# dig100-logic.net
KiCad netlist of a schematic drawn in EAGLE
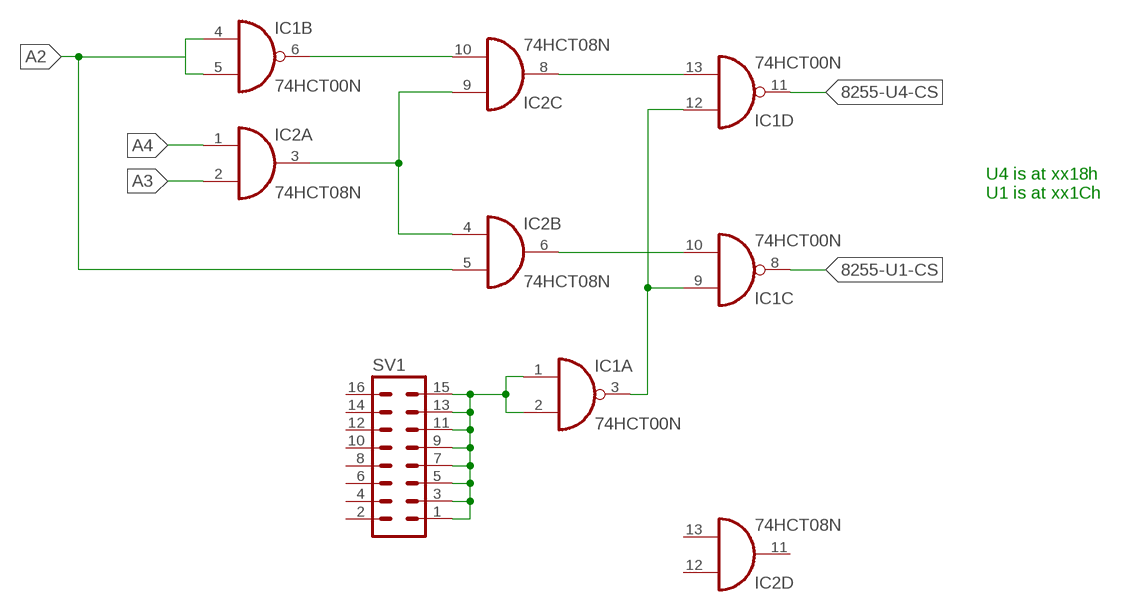
[diagram p0: schematic, sheet 1]

(export (version "E")
  (design (tool "Eeschema 10.0.6"))
  (components
    (comp (ref "IC1")
      (value "74HCT00N")
      (footprint "eagle-import:DIL14")
      (libsource (lib "eagle-import") (part "7400NHCT"))
    )
    (comp (ref "IC2")
      (value "74HCT08N")
      (footprint "eagle-import:DIL14")
      (libsource (lib "eagle-import") (part "7408NHCT"))
    )
    (comp (ref "SV1")
      (value "MA08-2")
      (footprint "eagle-import:MA08-2")
      (libsource (lib "eagle-import") (part "MA08-2"))
    )
  )
  (nets
    (net (code "1") (name "8255-U1-CS") (class "Default")
      (node (ref "IC1") (pin "8") (pinfunction "O_8") (pintype "output"))
    )
    (net (code "2") (name "8255-U4-CS") (class "Default")
      (node (ref "IC1") (pin "11") (pinfunction "O_11") (pintype "output"))
    )
    (net (code "3") (name "A2") (class "Default")
      (node (ref "IC1") (pin "4") (pinfunction "I0_4") (pintype "input"))
      (node (ref "IC1") (pin "5") (pinfunction "I1_5") (pintype "input"))
      (node (ref "IC2") (pin "5") (pinfunction "I1_5") (pintype "input"))
    )
    (net (code "4") (name "A3") (class "Default")
      (node (ref "IC2") (pin "2") (pinfunction "I1_2") (pintype "input"))
    )
    (net (code "5") (name "A4") (class "Default")
      (node (ref "IC2") (pin "1") (pinfunction "I0_1") (pintype "input"))
    )
    (net (code "6") (name "Net-(IC1A-I0)") (class "Default")
      (node (ref "IC1") (pin "1") (pinfunction "I0_1") (pintype "input"))
      (node (ref "IC1") (pin "2") (pinfunction "I1_2") (pintype "input"))
      (node (ref "SV1") (pin "1") (pinfunction "1_1") (pintype "passive"))
      (node (ref "SV1") (pin "11") (pinfunction "11_11") (pintype "passive"))
      (node (ref "SV1") (pin "13") (pinfunction "13_13") (pintype "passive"))
      (node (ref "SV1") (pin "15") (pinfunction "15_15") (pintype "passive"))
      (node (ref "SV1") (pin "3") (pinfunction "3_3") (pintype "passive"))
      (node (ref "SV1") (pin "5") (pinfunction "5_5") (pintype "passive"))
      (node (ref "SV1") (pin "7") (pinfunction "7_7") (pintype "passive"))
      (node (ref "SV1") (pin "9") (pinfunction "9_9") (pintype "passive"))
    )
    (net (code "7") (name "Net-(IC1A-O)") (class "Default")
      (node (ref "IC1") (pin "12") (pinfunction "I0_12") (pintype "input"))
      (node (ref "IC1") (pin "3") (pinfunction "O_3") (pintype "output"))
      (node (ref "IC1") (pin "9") (pinfunction "I0_9") (pintype "input"))
    )
    (net (code "8") (name "Net-(IC1B-O)") (class "Default")
      (node (ref "IC1") (pin "6") (pinfunction "O_6") (pintype "output"))
      (node (ref "IC2") (pin "10") (pinfunction "I1_10") (pintype "input"))
    )
    (net (code "9") (name "Net-(IC1C-I1)") (class "Default")
      (node (ref "IC1") (pin "10") (pinfunction "I1_10") (pintype "input"))
      (node (ref "IC2") (pin "6") (pinfunction "O_6") (pintype "output"))
    )
    (net (code "10") (name "Net-(IC1D-I1)") (class "Default")
      (node (ref "IC1") (pin "13") (pinfunction "I1_13") (pintype "input"))
      (node (ref "IC2") (pin "8") (pinfunction "O_8") (pintype "output"))
    )
    (net (code "11") (name "Net-(IC2A-O)") (class "Default")
      (node (ref "IC2") (pin "3") (pinfunction "O_3") (pintype "output"))
      (node (ref "IC2") (pin "4") (pinfunction "I0_4") (pintype "input"))
      (node (ref "IC2") (pin "9") (pinfunction "I0_9") (pintype "input"))
    )
    (net (code "12") (name "unconnected-(IC2D-I0-Pad12)") (class "Default")
      (node (ref "IC2") (pin "12") (pinfunction "I0_12") (pintype "input"))
    )
    (net (code "13") (name "unconnected-(IC2D-I1-Pad13)") (class "Default")
      (node (ref "IC2") (pin "13") (pinfunction "I1_13") (pintype "input"))
    )
    (net (code "14") (name "unconnected-(IC2D-O-Pad11)") (class "Default")
      (node (ref "IC2") (pin "11") (pinfunction "O_11") (pintype "output"))
    )
    (net (code "15") (name "unconnected-(SV1-Pad2)") (class "Default")
      (node (ref "SV1") (pin "2") (pinfunction "2_2") (pintype "passive"))
    )
    (net (code "16") (name "unconnected-(SV1-Pad4)") (class "Default")
      (node (ref "SV1") (pin "4") (pinfunction "4_4") (pintype "passive"))
    )
    (net (code "17") (name "unconnected-(SV1-Pad6)") (class "Default")
      (node (ref "SV1") (pin "6") (pinfunction "6_6") (pintype "passive"))
    )
    (net (code "18") (name "unconnected-(SV1-Pad8)") (class "Default")
      (node (ref "SV1") (pin "8") (pinfunction "8_8") (pintype "passive"))
    )
    (net (code "19") (name "unconnected-(SV1-Pad10)") (class "Default")
      (node (ref "SV1") (pin "10") (pinfunction "10_10") (pintype "passive"))
    )
    (net (code "20") (name "unconnected-(SV1-Pad12)") (class "Default")
      (node (ref "SV1") (pin "12") (pinfunction "12_12") (pintype "passive"))
    )
    (net (code "21") (name "unconnected-(SV1-Pad14)") (class "Default")
      (node (ref "SV1") (pin "14") (pinfunction "14_14") (pintype "passive"))
    )
    (net (code "22") (name "unconnected-(SV1-Pad16)") (class "Default")
      (node (ref "SV1") (pin "16") (pinfunction "16_16") (pintype "passive"))
    )
  )
)
